# pressureSensor.net
KiCad netlist of a schematic drawn in EAGLE
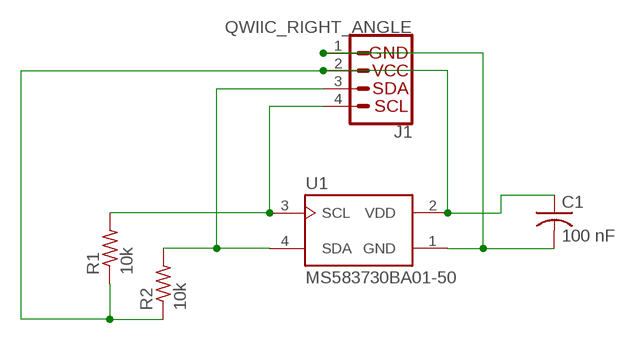
[diagram p0: schematic, sheet 1]

(export (version "E")
  (design (tool "Eeschema 10.0.6"))
  (components
    (comp (ref "C1")
      (value "100 nF")
      (footprint "eagle-import:C1206")
      (libsource (lib "eagle-import") (part "C-USC1206"))
    )
    (comp (ref "J1")
      (value "QWIIC_RIGHT_ANGLE")
      (footprint "eagle-import:JST04_1MM_RA")
      (libsource (lib "eagle-import") (part "QWIIC_CONNECTORJS-1MM"))
    )
    (comp (ref "R1")
      (value "10k")
      (footprint "eagle-import:M1206")
      (libsource (lib "eagle-import") (part "R-US_M1206"))
    )
    (comp (ref "R2")
      (value "10k")
      (footprint "eagle-import:M1206")
      (libsource (lib "eagle-import") (part "R-US_M1206"))
    )
    (comp (ref "U1")
      (value "MS583730BA01-50")
      (footprint "eagle-import:TE_MS583730BA01-50")
      (fields (field (name "DIGI-KEY_PART_NUMBER") "223-1704-1-ND") (field (name "MF") "TE Connectivity"))
      (libsource (lib "eagle-import") (part "MS583730BA01-50"))
    )
  )
  (nets
    (net (code "1") (name "Net-(U1-GND)") (class "Default")
      (node (ref "C1") (pin "2") (pinfunction "2_2") (pintype "passive"))
      (node (ref "J1") (pin "1") (pinfunction "1_1") (pintype "power_in"))
      (node (ref "U1") (pin "1") (pinfunction "GND_1") (pintype "power_in"))
    )
    (net (code "2") (name "Net-(U1-SCL)") (class "Default")
      (node (ref "J1") (pin "4") (pinfunction "4_4") (pintype "passive"))
      (node (ref "R1") (pin "2") (pinfunction "2_2") (pintype "passive"))
      (node (ref "U1") (pin "3") (pinfunction "SCL_3") (pintype "input"))
    )
    (net (code "3") (name "Net-(U1-SDA)") (class "Default")
      (node (ref "J1") (pin "3") (pinfunction "3_3") (pintype "passive"))
      (node (ref "R2") (pin "2") (pinfunction "2_2") (pintype "passive"))
      (node (ref "U1") (pin "4") (pinfunction "SDA_4") (pintype "bidirectional"))
    )
    (net (code "4") (name "Net-(U1-VDD)") (class "Default")
      (node (ref "C1") (pin "1") (pinfunction "1_1") (pintype "passive"))
      (node (ref "J1") (pin "2") (pinfunction "2_2") (pintype "power_in"))
      (node (ref "R1") (pin "1") (pinfunction "1_1") (pintype "passive"))
      (node (ref "R2") (pin "1") (pinfunction "1_1") (pintype "passive"))
      (node (ref "U1") (pin "2") (pinfunction "VDD_2") (pintype "power_in"))
    )
  )
)
